# shield.net
KiCad netlist of a schematic drawn in Altium Designer
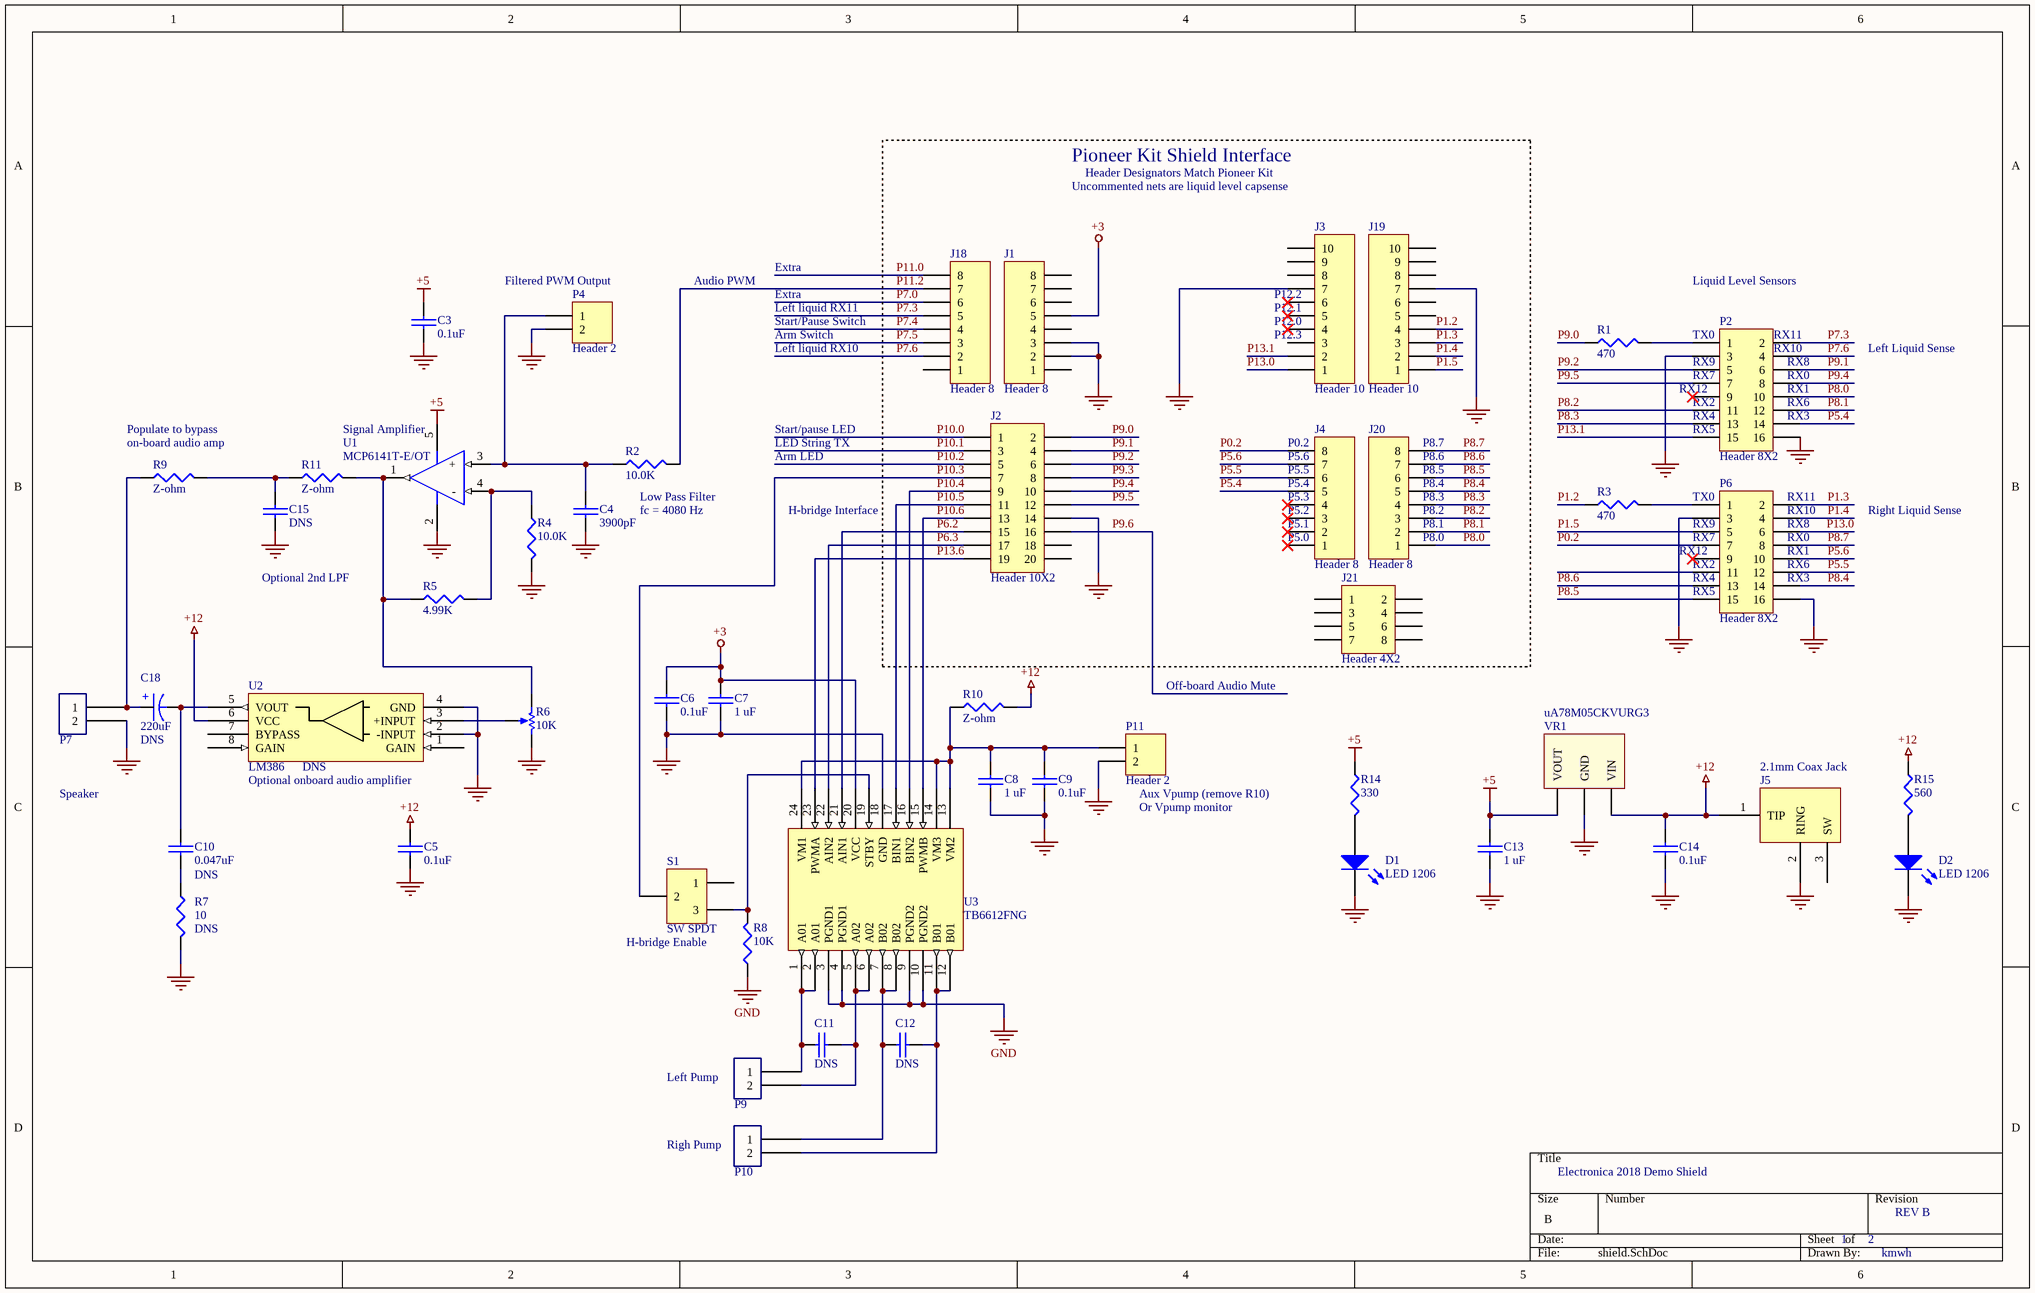
[diagram p0: shield.SchDoc]

(export (version "E")
  (design (tool "Eeschema 10.0.6"))
  (components
    (comp (ref "C3")
      (value "0.1uF")
      (footprint "C0603")
      (description "CAP, CER, 0.1UF, 50V, 10%, X7R, 0603")
      (libsource (lib "phantron-discretes") (part "CAP, CER, 0.1uF 0603"))
    )
    (comp (ref "C4")
      (value "3900pF")
      (footprint "C0603")
      (description "CAP, CER, blankUF, 6.3v, 10%, X5R, 0603")
      (libsource (lib "phantron-discretes") (part "CAP, CER, BLANK, 0603"))
    )
    (comp (ref "C5")
      (value "0.1uF")
      (footprint "C0603")
      (description "CAP, CER, 0.1UF, 50V, 10%, X7R, 0603")
      (libsource (lib "phantron-discretes") (part "CAP, CER, 0.1uF 0603"))
    )
    (comp (ref "C6")
      (value "0.1uF")
      (footprint "C0603")
      (description "CAP, CER, 0.1UF, 50V, 10%, X7R, 0603")
      (libsource (lib "phantron-discretes") (part "CAP, CER, 0.1uF 0603"))
    )
    (comp (ref "C7")
      (value "1 uF")
      (footprint "C0805")
      (description "CAP, CER, 1UF, 16v, 10%, X5R, 0805")
      (libsource (lib "phantron-discretes") (part "CAP, CER, 1UF, 0805"))
    )
    (comp (ref "C8")
      (value "1 uF")
      (footprint "C0805")
      (description "CAP, CER, 1UF, 16v, 10%, X5R, 0805")
      (libsource (lib "phantron-discretes") (part "CAP, CER, 1UF, 0805"))
    )
    (comp (ref "C9")
      (value "0.1uF")
      (footprint "C0603")
      (description "CAP, CER, 0.1UF, 50V, 10%, X7R, 0603")
      (libsource (lib "phantron-discretes") (part "CAP, CER, 0.1uF 0603"))
    )
    (comp (ref "C10")
      (value "0.047uF")
      (footprint "C0603")
      (description "CAP, CER, blankUF, 6.3v, 10%, X5R, 0603")
      (libsource (lib "phantron-discretes") (part "CAP, CER, BLANK, 0603"))
    )
    (comp (ref "C11")
      (value "DNS")
      (footprint "C0805")
      (description "CAP, CER, 1UF, 16v, 10%, X5R, 0805")
      (libsource (lib "phantron-discretes") (part "CAP, CER, 1UF, 0805"))
    )
    (comp (ref "C12")
      (value "DNS")
      (footprint "C0805")
      (description "CAP, CER, 1UF, 16v, 10%, X5R, 0805")
      (libsource (lib "phantron-discretes") (part "CAP, CER, 1UF, 0805"))
    )
    (comp (ref "C13")
      (value "1 uF")
      (footprint "C0805")
      (description "CAP, CER, 1UF, 16v, 10%, X5R, 0805")
      (libsource (lib "phantron-discretes") (part "CAP, CER, 1UF, 0805"))
    )
    (comp (ref "C14")
      (value "0.1uF")
      (footprint "C0603")
      (description "CAP, CER, 0.1UF, 50V, 10%, X7R, 0603")
      (libsource (lib "phantron-discretes") (part "CAP, CER, 0.1uF 0603"))
    )
    (comp (ref "C15")
      (value "DNS")
      (footprint "C0603")
      (description "CAP, CER, blankUF, 6.3v, 10%, X5R, 0603")
      (libsource (lib "phantron-discretes") (part "CAP, CER, BLANK, 0603"))
    )
    (comp (ref "C18")
      (value "220uF")
      (footprint "RadCap.98")
      (description "CAP, 220uF, 10V, ELEC, RAD")
      (fields (field (name "Comment") "11-000010-ARD"))
      (libsource (lib "00000000") (part "11-000010-ARD"))
    )
    (comp (ref "D1")
      (value "LED 1206")
      (footprint "3216[1206]")
      (fields (field (name "PUBLISHER") "Altium Limited"))
      (libsource (lib "Phantron") (part "LED 1206"))
    )
    (comp (ref "D2")
      (value "LED 1206")
      (footprint "3216[1206]")
      (fields (field (name "PUBLISHER") "Altium Limited"))
      (libsource (lib "Phantron") (part "LED 1206"))
    )
    (comp (ref "J1")
      (value "Header 8")
      (footprint "HDR1X8")
      (description "Header, 8-Pin")
      (fields (field (name "PUBLISHER") "Altium Limited"))
      (libsource (lib "") (part "Header 8_1"))
    )
    (comp (ref "J2")
      (value "Header 10X2")
      (footprint "HDR2X10")
      (description "Header, 10-Pin, Dual row")
      (fields (field (name "PUBLISHER") "Altium Limited"))
      (libsource (lib "Miscellaneous Connectors") (part "Header 10X2"))
    )
    (comp (ref "J3")
      (value "Header 10")
      (footprint "HDR1X10")
      (description "Header, 10-Pin")
      (fields (field (name "PUBLISHER") "Altium Limited"))
      (libsource (lib "Miscellaneous Connectors") (part "Header 10"))
    )
    (comp (ref "J4")
      (value "Header 8")
      (footprint "HDR1X8")
      (description "Header, 8-Pin")
      (fields (field (name "PUBLISHER") "Altium Limited"))
      (libsource (lib "Miscellaneous Connectors") (part "Header 8"))
    )
    (comp (ref "J5")
      (value "2.1mm Coax Jack")
      (footprint "Phantron:COAX_JACK_ALL")
      (libsource (lib "Phantron") (part "2.1mm Coax Jack"))
    )
    (comp (ref "J18")
      (value "Header 8")
      (footprint "HDR1X8")
      (description "Header, 8-Pin")
      (fields (field (name "PUBLISHER") "Altium Limited"))
      (libsource (lib "Miscellaneous Connectors") (part "Header 8"))
    )
    (comp (ref "J19")
      (value "Header 10")
      (footprint "HDR1X10")
      (description "Header, 10-Pin")
      (fields (field (name "PUBLISHER") "Altium Limited"))
      (libsource (lib "") (part "Header 10_1"))
    )
    (comp (ref "J20")
      (value "Header 8")
      (footprint "HDR1X8")
      (description "Header, 8-Pin")
      (fields (field (name "PUBLISHER") "Altium Limited"))
      (libsource (lib "") (part "Header 8_1"))
    )
    (comp (ref "J21")
      (value "Header 4X2")
      (footprint "HDR2X4")
      (description "Header, 4-Pin, Dual row")
      (fields (field (name "PUBLISHER") "Altium Limited"))
      (libsource (lib "Miscellaneous Connectors") (part "Header 4X2"))
    )
    (comp (ref "P2")
      (value "Header 8X2")
      (footprint "HDR2X8")
      (description "Header, 8-Pin, Dual row")
      (fields (field (name "PUBLISHER") "Altium Limited"))
      (libsource (lib "Miscellaneous Connectors") (part "Header 8X2"))
    )
    (comp (ref "P4")
      (value "Header 2")
      (footprint "HDR1X2")
      (description "Header, 2-Pin")
      (fields (field (name "PUBLISHER") "Altium Limited"))
      (libsource (lib "Miscellaneous Connectors") (part "Header 2"))
    )
    (comp (ref "P6")
      (value "Header 8X2")
      (footprint "HDR2X8")
      (description "Header, 8-Pin, Dual row")
      (fields (field (name "PUBLISHER") "Altium Limited"))
      (libsource (lib "Miscellaneous Connectors") (part "Header 8X2"))
    )
    (comp (ref "P7")
      (value "Connector, 0.138\", 2")
      (footprint "Phantron:connector-0.138-2pin")
      (description "Connector, 0.138\", 2 pin")
      (libsource (lib "Phantron") (part "Connector, 0.138{dblquote}, 2"))
    )
    (comp (ref "P9")
      (value "Connector, 0.138\", 2")
      (footprint "Phantron:connector-0.138-2pin")
      (description "Connector, 0.138\", 2 pin")
      (libsource (lib "Phantron") (part "Connector, 0.138{dblquote}, 2"))
    )
    (comp (ref "P10")
      (value "Connector, 0.138\", 2")
      (footprint "Phantron:connector-0.138-2pin")
      (description "Connector, 0.138\", 2 pin")
      (libsource (lib "Phantron") (part "Connector, 0.138{dblquote}, 2"))
    )
    (comp (ref "P11")
      (value "Header 2")
      (footprint "HDR1X2")
      (description "Header, 2-Pin")
      (fields (field (name "PUBLISHER") "Altium Limited"))
      (libsource (lib "Miscellaneous Connectors") (part "Header 2"))
    )
    (comp (ref "R1")
      (value "470")
      (footprint "R0603")
      (description "RES, BLANK OHM, 1/10W, 1%, 0603 SMD")
      (libsource (lib "phantron-discretes") (part "RES, BLANK, 0603"))
    )
    (comp (ref "R2")
      (value "10.0K")
      (footprint "R0603")
      (description "RES, BLANK OHM, 1/10W, 1%, 0603 SMD")
      (libsource (lib "phantron-discretes") (part "RES, BLANK, 0603"))
    )
    (comp (ref "R3")
      (value "470")
      (footprint "R0603")
      (description "RES, BLANK OHM, 1/10W, 1%, 0603 SMD")
      (libsource (lib "phantron-discretes") (part "RES, BLANK, 0603"))
    )
    (comp (ref "R4")
      (value "10.0K")
      (footprint "R0603")
      (description "RES, BLANK OHM, 1/10W, 1%, 0603 SMD")
      (libsource (lib "phantron-discretes") (part "RES, BLANK, 0603"))
    )
    (comp (ref "R5")
      (value "4.99K")
      (footprint "R0603")
      (description "RES, BLANK OHM, 1/10W, 1%, 0603 SMD")
      (libsource (lib "phantron-discretes") (part "RES, BLANK, 0603"))
    )
    (comp (ref "R6")
      (value "10K")
      (footprint "TrimmerPot")
      (description "Potentiometer")
      (fields (field (name "Comment") "RPot") (field (name "PUBLISHER") "Altium Limited"))
      (libsource (lib "Miscellaneous Devices") (part "RPot"))
    )
    (comp (ref "R7")
      (value "10")
      (footprint "R0603")
      (description "RES, BLANK OHM, 1/10W, 1%, 0603 SMD")
      (libsource (lib "phantron-discretes") (part "RES, BLANK, 0603"))
    )
    (comp (ref "R8")
      (value "10K")
      (footprint "R0603")
      (description "RES, BLANK OHM, 1/10W, 1%, 0603 SMD")
      (libsource (lib "phantron-discretes") (part "RES, BLANK, 0603"))
    )
    (comp (ref "R9")
      (value "Z-ohm")
      (footprint "R0603")
      (description "RES, BLANK OHM, 1/10W, 1%, 0603 SMD")
      (libsource (lib "phantron-discretes") (part "RES, BLANK, 0603"))
    )
    (comp (ref "R10")
      (value "Z-ohm")
      (footprint "R0603")
      (description "RES, BLANK OHM, 1/10W, 1%, 0603 SMD")
      (libsource (lib "phantron-discretes") (part "RES, BLANK, 0603"))
    )
    (comp (ref "R11")
      (value "Z-ohm")
      (footprint "R0603")
      (description "RES, BLANK OHM, 1/10W, 1%, 0603 SMD")
      (libsource (lib "phantron-discretes") (part "RES, BLANK, 0603"))
    )
    (comp (ref "R14")
      (value "330")
      (footprint "R0603")
      (description "RES, BLANK OHM, 1/10W, 1%, 0603 SMD")
      (libsource (lib "phantron-discretes") (part "RES, BLANK, 0603"))
    )
    (comp (ref "R15")
      (value "560")
      (footprint "R0603")
      (description "RES, BLANK OHM, 1/10W, 1%, 0603 SMD")
      (libsource (lib "phantron-discretes") (part "RES, BLANK, 0603"))
    )
    (comp (ref "S1")
      (value "SW SPDT")
      (footprint "HDR1X3")
      (description "Header, 3-Pin")
      (fields (field (name "PUBLISHER") "Altium Limited"))
      (libsource (lib "Miscellaneous Connectors") (part "Header 3"))
    )
    (comp (ref "U1")
      (value "MCP6141T-E/OT")
      (footprint "SOT23-5")
      (description "IC OPAMP SINGLE MCP6141 SOT23-5")
      (fields (field (name "MFG") "Microchip"))
      (libsource (lib "Phantron") (part "MCP6141"))
    )
    (comp (ref "U2")
      (value "LM386")
      (footprint "Phantron:SO8")
      (description "LM386MX")
      (fields (field (name "MFG") "TI"))
      (libsource (lib "Phantron") (part "LM386MX"))
    )
    (comp (ref "U3")
      (value "TB6612FNG")
      (footprint "Phantron:SSOP-24")
      (fields (field (name "MFG") "Toshiba"))
      (libsource (lib "Phantron") (part "TB6612FNG"))
    )
    (comp (ref "VR1")
      (value "uA78M05CKVURG3")
      (footprint "TO-252-AB(Dpak)")
      (libsource (lib "Phantron") (part "uA78M05CKVURG3"))
    )
  )
  (nets
    (net (code "1") (name "+3") (class "Default")
      (node (ref "C6") (pin "1") (pinfunction "A_1") (pintype "passive"))
      (node (ref "C7") (pin "1") (pinfunction "A_1") (pintype "passive"))
      (node (ref "J1") (pin "5") (pinfunction "5_5") (pintype "passive"))
      (node (ref "U3") (pin "20") (pinfunction "VCC_20") (pintype "power_in"))
    )
    (net (code "2") (name "+5") (class "Default")
      (node (ref "C13") (pin "1") (pinfunction "A_1") (pintype "passive"))
      (node (ref "C3") (pin "1") (pinfunction "A_1") (pintype "passive"))
      (node (ref "R14") (pin "1") (pinfunction "A_1") (pintype "passive"))
      (node (ref "U1") (pin "5") (pinfunction "VCC_5") (pintype "power_in"))
      (node (ref "VR1") (pin "3") (pinfunction "VOUT_3") (pintype "passive"))
    )
    (net (code "3") (name "+12") (class "Default")
      (node (ref "C14") (pin "1") (pinfunction "A_1") (pintype "passive"))
      (node (ref "C5") (pin "1") (pinfunction "A_1") (pintype "passive"))
      (node (ref "J5") (pin "1") (pinfunction "TIP_1") (pintype "passive"))
      (node (ref "R10") (pin "2") (pinfunction "B_2") (pintype "passive"))
      (node (ref "R15") (pin "1") (pinfunction "A_1") (pintype "passive"))
      (node (ref "U2") (pin "6") (pinfunction "VCC_6") (pintype "power_in"))
      (node (ref "VR1") (pin "1") (pinfunction "VIN_1") (pintype "passive"))
    )
    (net (code "4") (name "/P0.2") (class "Default")
      (node (ref "J4") (pin "8") (pinfunction "8_8") (pintype "passive"))
      (node (ref "P6") (pin "7") (pinfunction "7_7") (pintype "passive"))
    )
    (net (code "5") (name "/P1.2") (class "Default")
      (node (ref "J19") (pin "4") (pinfunction "4_4") (pintype "passive"))
      (node (ref "R3") (pin "1") (pinfunction "A_1") (pintype "passive"))
    )
    (net (code "6") (name "/P1.3") (class "Default")
      (node (ref "J19") (pin "3") (pinfunction "3_3") (pintype "passive"))
      (node (ref "P6") (pin "2") (pinfunction "2_2") (pintype "passive"))
    )
    (net (code "7") (name "/P1.4") (class "Default")
      (node (ref "J19") (pin "2") (pinfunction "2_2") (pintype "passive"))
      (node (ref "P6") (pin "4") (pinfunction "4_4") (pintype "passive"))
    )
    (net (code "8") (name "/P1.5") (class "Default")
      (node (ref "J19") (pin "1") (pinfunction "1_1") (pintype "passive"))
      (node (ref "P6") (pin "5") (pinfunction "5_5") (pintype "passive"))
    )
    (net (code "9") (name "/P5.4") (class "Default")
      (node (ref "J4") (pin "5") (pinfunction "5_5") (pintype "passive"))
      (node (ref "P2") (pin "14") (pinfunction "14_14") (pintype "passive"))
    )
    (net (code "10") (name "/P5.5") (class "Default")
      (node (ref "J4") (pin "6") (pinfunction "6_6") (pintype "passive"))
      (node (ref "P6") (pin "12") (pinfunction "12_12") (pintype "passive"))
    )
    (net (code "11") (name "/P5.6") (class "Default")
      (node (ref "J4") (pin "7") (pinfunction "7_7") (pintype "passive"))
      (node (ref "P6") (pin "10") (pinfunction "10_10") (pintype "passive"))
    )
    (net (code "12") (name "/P6.2") (class "Default")
      (node (ref "J2") (pin "15") (pinfunction "15_15") (pintype "passive"))
      (node (ref "U3") (pin "21") (pinfunction "AIN1_21") (pintype "input"))
    )
    (net (code "13") (name "/P6.3") (class "Default")
      (node (ref "J2") (pin "17") (pinfunction "17_17") (pintype "passive"))
      (node (ref "U3") (pin "22") (pinfunction "AIN2_22") (pintype "input"))
    )
    (net (code "14") (name "/P7.0") (class "Default")
      (node (ref "J18") (pin "6") (pinfunction "6_6") (pintype "passive"))
    )
    (net (code "15") (name "/P7.3") (class "Default")
      (node (ref "J18") (pin "5") (pinfunction "5_5") (pintype "passive"))
      (node (ref "P2") (pin "2") (pinfunction "2_2") (pintype "passive"))
    )
    (net (code "16") (name "/P7.4") (class "Default")
      (node (ref "J18") (pin "4") (pinfunction "4_4") (pintype "passive"))
    )
    (net (code "17") (name "/P7.5") (class "Default")
      (node (ref "J18") (pin "3") (pinfunction "3_3") (pintype "passive"))
    )
    (net (code "18") (name "/P7.6") (class "Default")
      (node (ref "J18") (pin "2") (pinfunction "2_2") (pintype "passive"))
      (node (ref "P2") (pin "4") (pinfunction "4_4") (pintype "passive"))
    )
    (net (code "19") (name "/P8.0") (class "Default")
      (node (ref "J20") (pin "1") (pinfunction "1_1") (pintype "passive"))
      (node (ref "P2") (pin "10") (pinfunction "10_10") (pintype "passive"))
    )
    (net (code "20") (name "/P8.1") (class "Default")
      (node (ref "J20") (pin "2") (pinfunction "2_2") (pintype "passive"))
      (node (ref "P2") (pin "12") (pinfunction "12_12") (pintype "passive"))
    )
    (net (code "21") (name "/P8.2") (class "Default")
      (node (ref "J20") (pin "3") (pinfunction "3_3") (pintype "passive"))
      (node (ref "P2") (pin "11") (pinfunction "11_11") (pintype "passive"))
    )
    (net (code "22") (name "/P8.3") (class "Default")
      (node (ref "J20") (pin "4") (pinfunction "4_4") (pintype "passive"))
      (node (ref "P2") (pin "13") (pinfunction "13_13") (pintype "passive"))
    )
    (net (code "23") (name "/P8.4") (class "Default")
      (node (ref "J20") (pin "5") (pinfunction "5_5") (pintype "passive"))
      (node (ref "P6") (pin "14") (pinfunction "14_14") (pintype "passive"))
    )
    (net (code "24") (name "/P8.5") (class "Default")
      (node (ref "J20") (pin "6") (pinfunction "6_6") (pintype "passive"))
      (node (ref "P6") (pin "15") (pinfunction "15_15") (pintype "passive"))
    )
    (net (code "25") (name "/P8.6") (class "Default")
      (node (ref "J20") (pin "7") (pinfunction "7_7") (pintype "passive"))
      (node (ref "P6") (pin "13") (pinfunction "13_13") (pintype "passive"))
    )
    (net (code "26") (name "/P8.7") (class "Default")
      (node (ref "J20") (pin "8") (pinfunction "8_8") (pintype "passive"))
      (node (ref "P6") (pin "8") (pinfunction "8_8") (pintype "passive"))
    )
    (net (code "27") (name "/P9.0") (class "Default")
      (node (ref "J2") (pin "2") (pinfunction "2_2") (pintype "passive"))
      (node (ref "R1") (pin "1") (pinfunction "A_1") (pintype "passive"))
    )
    (net (code "28") (name "/P9.1") (class "Default")
      (node (ref "J2") (pin "4") (pinfunction "4_4") (pintype "passive"))
      (node (ref "P2") (pin "6") (pinfunction "6_6") (pintype "passive"))
    )
    (net (code "29") (name "/P9.2") (class "Default")
      (node (ref "J2") (pin "6") (pinfunction "6_6") (pintype "passive"))
      (node (ref "P2") (pin "5") (pinfunction "5_5") (pintype "passive"))
    )
    (net (code "30") (name "/P9.3") (class "Default")
      (node (ref "J2") (pin "8") (pinfunction "8_8") (pintype "passive"))
    )
    (net (code "31") (name "/P9.4") (class "Default")
      (node (ref "J2") (pin "10") (pinfunction "10_10") (pintype "passive"))
      (node (ref "P2") (pin "8") (pinfunction "8_8") (pintype "passive"))
    )
    (net (code "32") (name "/P9.5") (class "Default")
      (node (ref "J2") (pin "12") (pinfunction "12_12") (pintype "passive"))
      (node (ref "P2") (pin "7") (pinfunction "7_7") (pintype "passive"))
    )
    (net (code "33") (name "/P9.6") (class "Default")
      (node (ref "J2") (pin "16") (pinfunction "16_16") (pintype "passive"))
    )
    (net (code "34") (name "/P10.0") (class "Default")
      (node (ref "J2") (pin "1") (pinfunction "1_1") (pintype "passive"))
    )
    (net (code "35") (name "/P10.1") (class "Default")
      (node (ref "J2") (pin "3") (pinfunction "3_3") (pintype "passive"))
    )
    (net (code "36") (name "/P10.2") (class "Default")
      (node (ref "J2") (pin "5") (pinfunction "5_5") (pintype "passive"))
    )
    (net (code "37") (name "/P10.3") (class "Default")
      (node (ref "J2") (pin "7") (pinfunction "7_7") (pintype "passive"))
      (node (ref "S1") (pin "2") (pinfunction "2_2") (pintype "passive"))
    )
    (net (code "38") (name "/P10.4") (class "Default")
      (node (ref "J2") (pin "9") (pinfunction "9_9") (pintype "passive"))
      (node (ref "U3") (pin "16") (pinfunction "BIN2_16") (pintype "input"))
    )
    (net (code "39") (name "/P10.5") (class "Default")
      (node (ref "J2") (pin "11") (pinfunction "11_11") (pintype "passive"))
      (node (ref "U3") (pin "17") (pinfunction "BIN1_17") (pintype "input"))
    )
    (net (code "40") (name "/P10.6") (class "Default")
      (node (ref "J2") (pin "13") (pinfunction "13_13") (pintype "passive"))
      (node (ref "U3") (pin "15") (pinfunction "PWMB_15") (pintype "input"))
    )
    (net (code "41") (name "/P11.0") (class "Default")
      (node (ref "J18") (pin "8") (pinfunction "8_8") (pintype "passive"))
    )
    (net (code "42") (name "/P11.2") (class "Default")
      (node (ref "J18") (pin "7") (pinfunction "7_7") (pintype "passive"))
      (node (ref "R2") (pin "2") (pinfunction "B_2") (pintype "passive"))
    )
    (net (code "43") (name "/P13.0") (class "Default")
      (node (ref "J3") (pin "1") (pinfunction "1_1") (pintype "passive"))
      (node (ref "P6") (pin "6") (pinfunction "6_6") (pintype "passive"))
    )
    (net (code "44") (name "/P13.1") (class "Default")
      (node (ref "J3") (pin "2") (pinfunction "2_2") (pintype "passive"))
      (node (ref "P2") (pin "15") (pinfunction "15_15") (pintype "passive"))
    )
    (net (code "45") (name "/P13.6") (class "Default")
      (node (ref "J2") (pin "19") (pinfunction "19_19") (pintype "passive"))
      (node (ref "U3") (pin "23") (pinfunction "PWMA_23") (pintype "input"))
    )
    (net (code "46") (name "GND") (class "Default")
      (node (ref "C13") (pin "2") (pinfunction "B_2") (pintype "passive"))
      (node (ref "C14") (pin "2") (pinfunction "B_2") (pintype "passive"))
      (node (ref "C15") (pin "2") (pinfunction "B_2") (pintype "passive"))
      (node (ref "C3") (pin "2") (pinfunction "B_2") (pintype "passive"))
      (node (ref "C4") (pin "2") (pinfunction "B_2") (pintype "passive"))
      (node (ref "C5") (pin "2") (pinfunction "B_2") (pintype "passive"))
      (node (ref "C6") (pin "2") (pinfunction "B_2") (pintype "passive"))
      (node (ref "C7") (pin "2") (pinfunction "B_2") (pintype "passive"))
      (node (ref "C8") (pin "2") (pinfunction "B_2") (pintype "passive"))
      (node (ref "C9") (pin "2") (pinfunction "B_2") (pintype "passive"))
      (node (ref "D1") (pin "2") (pinfunction "K_2") (pintype "passive"))
      (node (ref "D2") (pin "2") (pinfunction "K_2") (pintype "passive"))
      (node (ref "J1") (pin "2") (pinfunction "2_2") (pintype "passive"))
      (node (ref "J1") (pin "3") (pinfunction "3_3") (pintype "passive"))
      (node (ref "J19") (pin "7") (pinfunction "7_7") (pintype "passive"))
      (node (ref "J2") (pin "14") (pinfunction "14_14") (pintype "passive"))
      (node (ref "J3") (pin "7") (pinfunction "7_7") (pintype "passive"))
      (node (ref "J5") (pin "2") (pinfunction "RING_2") (pintype "passive"))
      (node (ref "P11") (pin "2") (pinfunction "2_2") (pintype "passive"))
      (node (ref "P2") (pin "16") (pinfunction "16_16") (pintype "passive"))
      (node (ref "P2") (pin "3") (pinfunction "3_3") (pintype "passive"))
      (node (ref "P4") (pin "2") (pinfunction "2_2") (pintype "passive"))
      (node (ref "P6") (pin "16") (pinfunction "16_16") (pintype "passive"))
      (node (ref "P6") (pin "3") (pinfunction "3_3") (pintype "passive"))
      (node (ref "P7") (pin "2") (pinfunction "2_2") (pintype "passive"))
      (node (ref "R4") (pin "2") (pinfunction "B_2") (pintype "passive"))
      (node (ref "R6") (pin "1") (pinfunction "TOP_1") (pintype "passive"))
      (node (ref "R7") (pin "2") (pinfunction "B_2") (pintype "passive"))
      (node (ref "R8") (pin "1") (pinfunction "A_1") (pintype "passive"))
      (node (ref "U1") (pin "2") (pinfunction "GND_2") (pintype "power_in"))
      (node (ref "U2") (pin "2") (pinfunction "-INPUT_2") (pintype "input"))
      (node (ref "U2") (pin "4") (pinfunction "GND_4") (pintype "power_in"))
      (node (ref "U3") (pin "10") (pinfunction "PGND2_10") (pintype "power_in"))
      (node (ref "U3") (pin "18") (pinfunction "GND_18") (pintype "power_in"))
      (node (ref "U3") (pin "3") (pinfunction "PGND1_3") (pintype "power_in"))
      (node (ref "U3") (pin "4") (pinfunction "PGND1_4") (pintype "power_in"))
      (node (ref "U3") (pin "9") (pinfunction "PGND2_9") (pintype "power_in"))
      (node (ref "VR1") (pin "4") (pinfunction "GND_4") (pintype "passive"))
    )
    (net (code "47") (name "Net-(C4-A)") (class "Default")
      (node (ref "C4") (pin "1") (pinfunction "A_1") (pintype "passive"))
      (node (ref "P4") (pin "1") (pinfunction "1_1") (pintype "passive"))
      (node (ref "R2") (pin "1") (pinfunction "A_1") (pintype "passive"))
      (node (ref "U1") (pin "3") (pinfunction "+_3") (pintype "input"))
    )
    (net (code "48") (name "Net-(C8-A)") (class "Default")
      (node (ref "C8") (pin "1") (pinfunction "A_1") (pintype "passive"))
      (node (ref "C9") (pin "1") (pinfunction "A_1") (pintype "passive"))
      (node (ref "P11") (pin "1") (pinfunction "1_1") (pintype "passive"))
      (node (ref "R10") (pin "1") (pinfunction "A_1") (pintype "passive"))
      (node (ref "U3") (pin "13") (pinfunction "VM2_13") (pintype "power_in"))
      (node (ref "U3") (pin "14") (pinfunction "VM3_14") (pintype "power_in"))
      (node (ref "U3") (pin "24") (pinfunction "VM1_24") (pintype "power_in"))
    )
    (net (code "49") (name "Net-(C10-A)") (class "Default")
      (node (ref "C10") (pin "1") (pinfunction "A_1") (pintype "passive"))
      (node (ref "C18") (pin "2") (pinfunction "NEGATIVE_2") (pintype "passive"))
      (node (ref "U2") (pin "5") (pinfunction "VOUT_5") (pintype "output"))
    )
    (net (code "50") (name "Net-(C10-B)") (class "Default")
      (node (ref "C10") (pin "2") (pinfunction "B_2") (pintype "passive"))
      (node (ref "R7") (pin "1") (pinfunction "A_1") (pintype "passive"))
    )
    (net (code "51") (name "Net-(C11-A)") (class "Default")
      (node (ref "C11") (pin "1") (pinfunction "A_1") (pintype "passive"))
      (node (ref "P9") (pin "1") (pinfunction "1_1") (pintype "passive"))
      (node (ref "U3") (pin "1") (pinfunction "A01_1") (pintype "output"))
      (node (ref "U3") (pin "2") (pinfunction "A01_2") (pintype "output"))
    )
    (net (code "52") (name "Net-(C11-B)") (class "Default")
      (node (ref "C11") (pin "2") (pinfunction "B_2") (pintype "passive"))
      (node (ref "P9") (pin "2") (pinfunction "2_2") (pintype "passive"))
      (node (ref "U3") (pin "5") (pinfunction "A02_5") (pintype "output"))
      (node (ref "U3") (pin "6") (pinfunction "A02_6") (pintype "output"))
    )
    (net (code "53") (name "Net-(C12-A)") (class "Default")
      (node (ref "C12") (pin "1") (pinfunction "A_1") (pintype "passive"))
      (node (ref "P10") (pin "1") (pinfunction "1_1") (pintype "passive"))
      (node (ref "U3") (pin "7") (pinfunction "B02_7") (pintype "output"))
      (node (ref "U3") (pin "8") (pinfunction "B02_8") (pintype "output"))
    )
    (net (code "54") (name "Net-(C12-B)") (class "Default")
      (node (ref "C12") (pin "2") (pinfunction "B_2") (pintype "passive"))
      (node (ref "P10") (pin "2") (pinfunction "2_2") (pintype "passive"))
      (node (ref "U3") (pin "11") (pinfunction "B01_11") (pintype "output"))
      (node (ref "U3") (pin "12") (pinfunction "B01_12") (pintype "output"))
    )
    (net (code "55") (name "Net-(C15-A)") (class "Default")
      (node (ref "C15") (pin "1") (pinfunction "A_1") (pintype "passive"))
      (node (ref "R11") (pin "1") (pinfunction "A_1") (pintype "passive"))
      (node (ref "R9") (pin "2") (pinfunction "B_2") (pintype "passive"))
    )
    (net (code "56") (name "Net-(C18-POSITIVE)") (class "Default")
      (node (ref "C18") (pin "1") (pinfunction "POSITIVE_1") (pintype "passive"))
      (node (ref "P7") (pin "1") (pinfunction "1_1") (pintype "passive"))
      (node (ref "R9") (pin "1") (pinfunction "A_1") (pintype "passive"))
    )
    (net (code "57") (name "Net-(D1-A)") (class "Default")
      (node (ref "D1") (pin "1") (pinfunction "A_1") (pintype "passive"))
      (node (ref "R14") (pin "2") (pinfunction "B_2") (pintype "passive"))
    )
    (net (code "58") (name "Net-(D2-A)") (class "Default")
      (node (ref "D2") (pin "1") (pinfunction "A_1") (pintype "passive"))
      (node (ref "R15") (pin "2") (pinfunction "B_2") (pintype "passive"))
    )
    (net (code "59") (name "Net-(R1-B)") (class "Default")
      (node (ref "P2") (pin "1") (pinfunction "1_1") (pintype "passive"))
      (node (ref "R1") (pin "2") (pinfunction "B_2") (pintype "passive"))
    )
    (net (code "60") (name "Net-(R3-B)") (class "Default")
      (node (ref "P6") (pin "1") (pinfunction "1_1") (pintype "passive"))
      (node (ref "R3") (pin "2") (pinfunction "B_2") (pintype "passive"))
    )
    (net (code "61") (name "Net-(R4-A)") (class "Default")
      (node (ref "R4") (pin "1") (pinfunction "A_1") (pintype "passive"))
      (node (ref "R5") (pin "2") (pinfunction "B_2") (pintype "passive"))
      (node (ref "U1") (pin "4") (pinfunction "-_4") (pintype "input"))
    )
    (net (code "62") (name "Net-(R6-TAP)") (class "Default")
      (node (ref "R6") (pin "2") (pinfunction "TAP_2") (pintype "passive"))
      (node (ref "U2") (pin "3") (pinfunction "+INPUT_3") (pintype "input"))
    )
    (net (code "63") (name "Net-(R8-B)") (class "Default")
      (node (ref "R8") (pin "2") (pinfunction "B_2") (pintype "passive"))
      (node (ref "S1") (pin "3") (pinfunction "3_3") (pintype "passive"))
      (node (ref "U3") (pin "19") (pinfunction "STBY_19") (pintype "input"))
    )
    (net (code "64") (name "Net-(R11-B)") (class "Default")
      (node (ref "R11") (pin "2") (pinfunction "B_2") (pintype "passive"))
      (node (ref "R5") (pin "1") (pinfunction "A_1") (pintype "passive"))
      (node (ref "R6") (pin "3") (pinfunction "BOT_3") (pintype "passive"))
      (node (ref "U1") (pin "1") (pinfunction "OUT_1") (pintype "output"))
    )
    (net (code "65") (name "unconnected-(J1-Pad1)") (class "Default")
      (node (ref "J1") (pin "1") (pinfunction "1_1") (pintype "passive"))
    )
    (net (code "66") (name "unconnected-(J1-Pad4)") (class "Default")
      (node (ref "J1") (pin "4") (pinfunction "4_4") (pintype "passive"))
    )
    (net (code "67") (name "unconnected-(J1-Pad6)") (class "Default")
      (node (ref "J1") (pin "6") (pinfunction "6_6") (pintype "passive"))
    )
    (net (code "68") (name "unconnected-(J1-Pad7)") (class "Default")
      (node (ref "J1") (pin "7") (pinfunction "7_7") (pintype "passive"))
    )
    (net (code "69") (name "unconnected-(J1-Pad8)") (class "Default")
      (node (ref "J1") (pin "8") (pinfunction "8_8") (pintype "passive"))
    )
    (net (code "70") (name "unconnected-(J2-Pad18)") (class "Default")
      (node (ref "J2") (pin "18") (pinfunction "18_18") (pintype "passive"))
    )
    (net (code "71") (name "unconnected-(J2-Pad20)") (class "Default")
      (node (ref "J2") (pin "20") (pinfunction "20_20") (pintype "passive"))
    )
    (net (code "72") (name "unconnected-(J3-Pad3)") (class "Default")
      (node (ref "J3") (pin "3") (pinfunction "3_3") (pintype "passive"))
    )
    (net (code "73") (name "unconnected-(J3-Pad4)") (class "Default")
      (node (ref "J3") (pin "4") (pinfunction "4_4") (pintype "passive+no_connect"))
    )
    (net (code "74") (name "unconnected-(J3-Pad5)") (class "Default")
      (node (ref "J3") (pin "5") (pinfunction "5_5") (pintype "passive+no_connect"))
    )
    (net (code "75") (name "unconnected-(J3-Pad6)") (class "Default")
      (node (ref "J3") (pin "6") (pinfunction "6_6") (pintype "passive+no_connect"))
    )
    (net (code "76") (name "unconnected-(J3-Pad8)") (class "Default")
      (node (ref "J3") (pin "8") (pinfunction "8_8") (pintype "passive"))
    )
    (net (code "77") (name "unconnected-(J3-Pad9)") (class "Default")
      (node (ref "J3") (pin "9") (pinfunction "9_9") (pintype "passive"))
    )
    (net (code "78") (name "unconnected-(J3-Pad10)") (class "Default")
      (node (ref "J3") (pin "10") (pinfunction "10_10") (pintype "passive"))
    )
    (net (code "79") (name "unconnected-(J4-Pad1)") (class "Default")
      (node (ref "J4") (pin "1") (pinfunction "1_1") (pintype "passive+no_connect"))
    )
    (net (code "80") (name "unconnected-(J4-Pad2)") (class "Default")
      (node (ref "J4") (pin "2") (pinfunction "2_2") (pintype "passive+no_connect"))
    )
    (net (code "81") (name "unconnected-(J4-Pad3)") (class "Default")
      (node (ref "J4") (pin "3") (pinfunction "3_3") (pintype "passive+no_connect"))
    )
    (net (code "82") (name "unconnected-(J4-Pad4)") (class "Default")
      (node (ref "J4") (pin "4") (pinfunction "4_4") (pintype "passive+no_connect"))
    )
    (net (code "83") (name "unconnected-(J5-SW-Pad3)") (class "Default")
      (node (ref "J5") (pin "3") (pinfunction "SW_3") (pintype "passive"))
    )
    (net (code "84") (name "unconnected-(J18-Pad1)") (class "Default")
      (node (ref "J18") (pin "1") (pinfunction "1_1") (pintype "passive"))
    )
    (net (code "85") (name "unconnected-(J19-Pad5)") (class "Default")
      (node (ref "J19") (pin "5") (pinfunction "5_5") (pintype "passive"))
    )
    (net (code "86") (name "unconnected-(J19-Pad6)") (class "Default")
      (node (ref "J19") (pin "6") (pinfunction "6_6") (pintype "passive"))
    )
    (net (code "87") (name "unconnected-(J19-Pad8)") (class "Default")
      (node (ref "J19") (pin "8") (pinfunction "8_8") (pintype "passive"))
    )
    (net (code "88") (name "unconnected-(J19-Pad9)") (class "Default")
      (node (ref "J19") (pin "9") (pinfunction "9_9") (pintype "passive"))
    )
    (net (code "89") (name "unconnected-(J19-Pad10)") (class "Default")
      (node (ref "J19") (pin "10") (pinfunction "10_10") (pintype "passive"))
    )
    (net (code "90") (name "unconnected-(J21-Pad1)") (class "Default")
      (node (ref "J21") (pin "1") (pinfunction "1_1") (pintype "passive"))
    )
    (net (code "91") (name "unconnected-(J21-Pad2)") (class "Default")
      (node (ref "J21") (pin "2") (pinfunction "2_2") (pintype "passive"))
    )
    (net (code "92") (name "unconnected-(J21-Pad3)") (class "Default")
      (node (ref "J21") (pin "3") (pinfunction "3_3") (pintype "passive"))
    )
    (net (code "93") (name "unconnected-(J21-Pad4)") (class "Default")
      (node (ref "J21") (pin "4") (pinfunction "4_4") (pintype "passive"))
    )
    (net (code "94") (name "unconnected-(J21-Pad5)") (class "Default")
      (node (ref "J21") (pin "5") (pinfunction "5_5") (pintype "passive"))
    )
    (net (code "95") (name "unconnected-(J21-Pad6)") (class "Default")
      (node (ref "J21") (pin "6") (pinfunction "6_6") (pintype "passive"))
    )
    (net (code "96") (name "unconnected-(J21-Pad7)") (class "Default")
      (node (ref "J21") (pin "7") (pinfunction "7_7") (pintype "passive"))
    )
    (net (code "97") (name "unconnected-(J21-Pad8)") (class "Default")
      (node (ref "J21") (pin "8") (pinfunction "8_8") (pintype "passive"))
    )
    (net (code "98") (name "unconnected-(P2-Pad9)") (class "Default")
      (node (ref "P2") (pin "9") (pinfunction "9_9") (pintype "passive+no_connect"))
    )
    (net (code "99") (name "unconnected-(P6-Pad9)") (class "Default")
      (node (ref "P6") (pin "9") (pinfunction "9_9") (pintype "passive+no_connect"))
    )
    (net (code "100") (name "unconnected-(P6-Pad11)") (class "Default")
      (node (ref "P6") (pin "11") (pinfunction "11_11") (pintype "passive"))
    )
    (net (code "101") (name "unconnected-(S1-Pad1)") (class "Default")
      (node (ref "S1") (pin "1") (pinfunction "1_1") (pintype "passive"))
    )
    (net (code "102") (name "unconnected-(U2-BYPASS-Pad7)") (class "Default")
      (node (ref "U2") (pin "7") (pinfunction "BYPASS_7") (pintype "passive"))
    )
    (net (code "103") (name "unconnected-(U2-GAIN-Pad1)") (class "Default")
      (node (ref "U2") (pin "1") (pinfunction "GAIN_1") (pintype "input"))
    )
    (net (code "104") (name "unconnected-(U2-GAIN-Pad8)") (class "Default")
      (node (ref "U2") (pin "8") (pinfunction "GAIN_8") (pintype "input"))
    )
  )
)
